# URESP_PULSER.net
KiCad netlist of a schematic drawn in Altium Designer
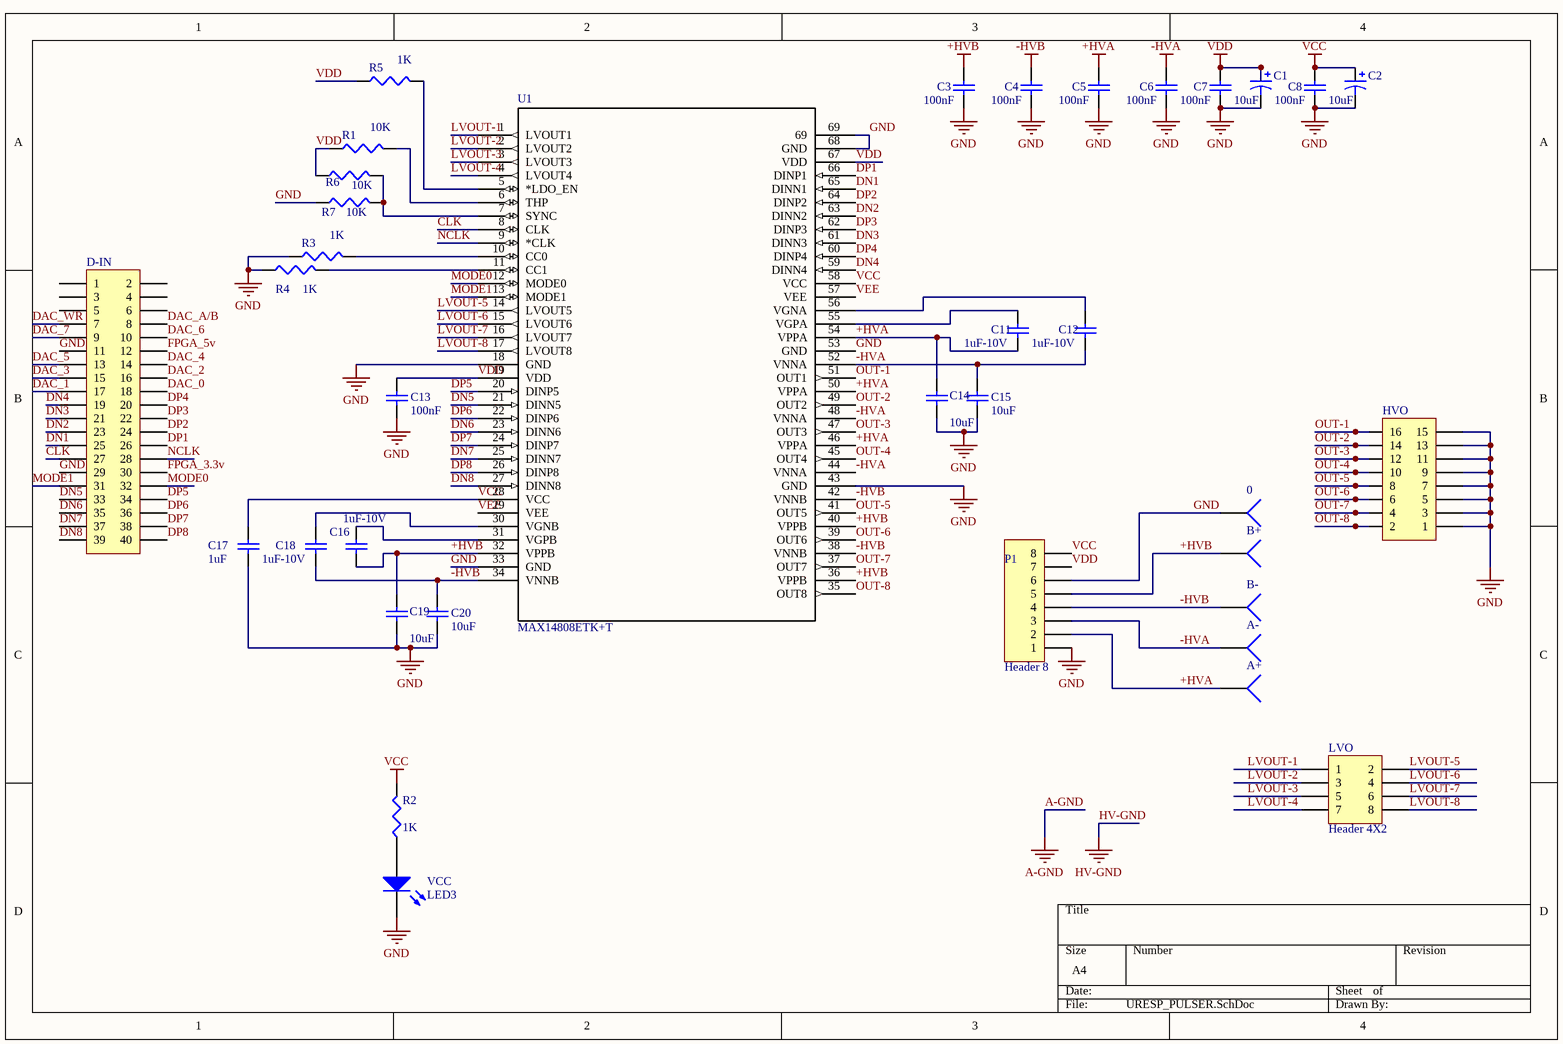
[diagram p0: URESP_PULSER.SchDoc]

(export (version "E")
  (design (tool "Eeschema 10.0.6"))
  (components
    (comp (ref "0")
      (value "~")
      (footprint "PIN1")
      (description "Socket")
      (fields (field (name "PUBLISHER") "Altium Limited"))
      (libsource (lib "Miscellaneous Connectors") (part "Socket"))
    )
    (comp (ref "A+")
      (value "~")
      (footprint "PIN1")
      (description "Socket")
      (fields (field (name "PUBLISHER") "Altium Limited"))
      (libsource (lib "Miscellaneous Connectors") (part "Socket"))
    )
    (comp (ref "A-")
      (value "~")
      (footprint "PIN1")
      (description "Socket")
      (fields (field (name "PUBLISHER") "Altium Limited"))
      (libsource (lib "Miscellaneous Connectors") (part "Socket"))
    )
    (comp (ref "B+")
      (value "~")
      (footprint "PIN1")
      (description "Socket")
      (fields (field (name "PUBLISHER") "Altium Limited"))
      (libsource (lib "Miscellaneous Connectors") (part "Socket"))
    )
    (comp (ref "B-")
      (value "~")
      (footprint "PIN1")
      (description "Socket")
      (fields (field (name "PUBLISHER") "Altium Limited"))
      (libsource (lib "Miscellaneous Connectors") (part "Socket"))
    )
    (comp (ref "C1")
      (value "10uF")
      (footprint "C1206")
      (description "Polarized Capacitor (Surface Mount)")
      (fields (field (name "PUBLISHER") "Altium Limited"))
      (libsource (lib "Miscellaneous Devices") (part "Cap Pol3"))
    )
    (comp (ref "C2")
      (value "10uF")
      (footprint "C1206")
      (description "Polarized Capacitor (Surface Mount)")
      (fields (field (name "PUBLISHER") "Altium Limited"))
      (libsource (lib "Miscellaneous Devices") (part "Cap Pol3"))
    )
    (comp (ref "C3")
      (value "100nF")
      (footprint "6-0805_M")
      (description "Capacitor (Semiconductor SIM Model)")
      (fields (field (name "PUBLISHER") "Altium Limited"))
      (libsource (lib "Miscellaneous Devices") (part "Cap Semi"))
    )
    (comp (ref "C4")
      (value "100nF")
      (footprint "6-0805_M")
      (description "Capacitor (Semiconductor SIM Model)")
      (fields (field (name "PUBLISHER") "Altium Limited"))
      (libsource (lib "Miscellaneous Devices") (part "Cap Semi"))
    )
    (comp (ref "C5")
      (value "100nF")
      (footprint "6-0805_M")
      (description "Capacitor (Semiconductor SIM Model)")
      (fields (field (name "PUBLISHER") "Altium Limited"))
      (libsource (lib "Miscellaneous Devices") (part "Cap Semi"))
    )
    (comp (ref "C6")
      (value "100nF")
      (footprint "6-0805_M")
      (description "Capacitor (Semiconductor SIM Model)")
      (fields (field (name "PUBLISHER") "Altium Limited"))
      (libsource (lib "Miscellaneous Devices") (part "Cap Semi"))
    )
    (comp (ref "C7")
      (value "100nF")
      (footprint "1608[0603]")
      (description "Capacitor (Semiconductor SIM Model)")
      (fields (field (name "PUBLISHER") "Altium Limited"))
      (libsource (lib "Miscellaneous Devices") (part "Cap Semi"))
    )
    (comp (ref "C8")
      (value "100nF")
      (footprint "1608[0603]")
      (description "Capacitor (Semiconductor SIM Model)")
      (fields (field (name "PUBLISHER") "Altium Limited"))
      (libsource (lib "Miscellaneous Devices") (part "Cap Semi"))
    )
    (comp (ref "C11")
      (value "1uF-10V")
      (footprint "1608[0603]")
      (description "Capacitor (Semiconductor SIM Model)")
      (fields (field (name "PUBLISHER") "Altium Limited"))
      (libsource (lib "Miscellaneous Devices") (part "Cap Semi"))
    )
    (comp (ref "C12")
      (value "1uF-10V")
      (footprint "1608[0603]")
      (description "Capacitor (Semiconductor SIM Model)")
      (fields (field (name "PUBLISHER") "Altium Limited"))
      (libsource (lib "Miscellaneous Devices") (part "Cap Semi"))
    )
    (comp (ref "C13")
      (value "100nF")
      (footprint "1608[0603]")
      (description "Capacitor (Semiconductor SIM Model)")
      (fields (field (name "PUBLISHER") "Altium Limited"))
      (libsource (lib "Miscellaneous Devices") (part "Cap Semi"))
    )
    (comp (ref "C14")
      (value "10uF")
      (footprint "CAPPR5-6.3X5")
      (description "Capacitor (Semiconductor SIM Model)")
      (fields (field (name "PUBLISHER") "Altium Limited"))
      (libsource (lib "Miscellaneous Devices") (part "Cap Semi"))
    )
    (comp (ref "C15")
      (value "10uF")
      (footprint "CAPPR5-6.3x5")
      (description "Capacitor (Semiconductor SIM Model)")
      (fields (field (name "PUBLISHER") "Altium Limited"))
      (libsource (lib "Miscellaneous Devices") (part "Cap Semi"))
    )
    (comp (ref "C16")
      (value "1uF-10V")
      (footprint "1608[0603]")
      (description "Capacitor (Semiconductor SIM Model)")
      (fields (field (name "PUBLISHER") "Altium Limited"))
      (libsource (lib "Miscellaneous Devices") (part "Cap Semi"))
    )
    (comp (ref "C17")
      (value "1uF")
      (footprint "1608[0603]")
      (description "Capacitor (Semiconductor SIM Model)")
      (fields (field (name "PUBLISHER") "Altium Limited"))
      (libsource (lib "Miscellaneous Devices") (part "Cap Semi"))
    )
    (comp (ref "C18")
      (value "1uF-10V")
      (footprint "1608[0603]")
      (description "Capacitor (Semiconductor SIM Model)")
      (fields (field (name "PUBLISHER") "Altium Limited"))
      (libsource (lib "Miscellaneous Devices") (part "Cap Semi"))
    )
    (comp (ref "C19")
      (value "10uF")
      (footprint "CAPPR5-6.3X5")
      (description "Capacitor (Semiconductor SIM Model)")
      (fields (field (name "PUBLISHER") "Altium Limited"))
      (libsource (lib "Miscellaneous Devices") (part "Cap Semi"))
    )
    (comp (ref "C20")
      (value "10uF")
      (footprint "CAPPR5-6.3X5")
      (description "Capacitor (Semiconductor SIM Model)")
      (fields (field (name "PUBLISHER") "Altium Limited"))
      (libsource (lib "Miscellaneous Devices") (part "Cap Semi"))
    )
    (comp (ref "D-IN")
      (value "~")
      (footprint "HDR2X20")
      (description "Header, 20-Pin, Dual row")
      (fields (field (name "PUBLISHER") "Altium Limited"))
      (libsource (lib "Miscellaneous Connectors") (part "Header 20X2"))
    )
    (comp (ref "HVO")
      (value "~")
      (footprint "HDR2X8")
      (description "Header, 8-Pin, Dual row, Right Angle")
      (fields (field (name "PUBLISHER") "Altium Limited"))
      (libsource (lib "Miscellaneous Connectors") (part "Header 8X2H"))
    )
    (comp (ref "LVO")
      (value "Header 4X2")
      (footprint "HDR2X4")
      (description "Header, 4-Pin, Dual row")
      (fields (field (name "PUBLISHER") "Altium Limited"))
      (libsource (lib "Miscellaneous Connectors") (part "Header 4X2"))
    )
    (comp (ref "P1")
      (value "Header 8")
      (footprint "HDR1X8")
      (description "Header, 8-Pin")
      (fields (field (name "PUBLISHER") "Altium Limited"))
      (libsource (lib "Miscellaneous Connectors") (part "Header 8"))
    )
    (comp (ref "R1")
      (value "10K")
      (footprint "J1-0603")
      (description "Resistor")
      (fields (field (name "PUBLISHER") "Altium Limited"))
      (libsource (lib "Miscellaneous Devices") (part "Res3"))
    )
    (comp (ref "R2")
      (value "1K")
      (footprint "J1-0603")
      (description "Resistor")
      (fields (field (name "PUBLISHER") "Altium Limited"))
      (libsource (lib "Miscellaneous Devices") (part "Res3"))
    )
    (comp (ref "R3")
      (value "1K")
      (footprint "J1-0603")
      (description "Resistor")
      (fields (field (name "PUBLISHER") "Altium Limited"))
      (libsource (lib "Miscellaneous Devices") (part "Res3"))
    )
    (comp (ref "R4")
      (value "1K")
      (footprint "J1-0603")
      (description "Resistor")
      (fields (field (name "PUBLISHER") "Altium Limited"))
      (libsource (lib "Miscellaneous Devices") (part "Res3"))
    )
    (comp (ref "R5")
      (value "1K")
      (footprint "J1-0603")
      (description "Resistor")
      (fields (field (name "PUBLISHER") "Altium Limited"))
      (libsource (lib "Miscellaneous Devices") (part "Res3"))
    )
    (comp (ref "R6")
      (value "10K")
      (footprint "J1-0603")
      (description "Resistor")
      (fields (field (name "PUBLISHER") "Altium Limited"))
      (libsource (lib "Miscellaneous Devices") (part "Res3"))
    )
    (comp (ref "R7")
      (value "10K")
      (footprint "J1-0603")
      (description "Resistor")
      (fields (field (name "PUBLISHER") "Altium Limited"))
      (libsource (lib "Miscellaneous Devices") (part "Res3"))
    )
    (comp (ref "U1")
      (value "MAX14808ETK+T")
      (footprint "21-0142E_T6800-2")
      (description "Imported")
      (libsource (lib "max14808") (part "MAX14808ETK+T"))
    )
    (comp (ref "VCC")
      (value "LED3")
      (footprint "6-0805_M")
      (description "Typical BLUE SiC LED")
      (fields (field (name "PUBLISHER") "Altium Limited"))
      (libsource (lib "Miscellaneous Devices") (part "LED3"))
    )
  )
  (nets
    (net (code "1") (name "+HVA") (class "Default")
      (node (ref "A+") (pin "1") (pinfunction "1_1") (pintype "passive"))
      (node (ref "C11") (pin "1") (pinfunction "1_1") (pintype "passive"))
      (node (ref "C14") (pin "1") (pinfunction "1_1") (pintype "passive"))
      (node (ref "C5") (pin "2") (pinfunction "2_2") (pintype "passive"))
      (node (ref "P1") (pin "2") (pinfunction "2_2") (pintype "passive"))
      (node (ref "U1") (pin "46") (pinfunction "VPPA_46") (pintype "power_in"))
      (node (ref "U1") (pin "50") (pinfunction "VPPA_50") (pintype "power_in"))
      (node (ref "U1") (pin "54") (pinfunction "VPPA_54") (pintype "power_in"))
    )
    (net (code "2") (name "+HVB") (class "Default")
      (node (ref "B+") (pin "1") (pinfunction "1_1") (pintype "passive"))
      (node (ref "C16") (pin "1") (pinfunction "1_1") (pintype "passive"))
      (node (ref "C19") (pin "1") (pinfunction "1_1") (pintype "passive"))
      (node (ref "C3") (pin "2") (pinfunction "2_2") (pintype "passive"))
      (node (ref "P1") (pin "5") (pinfunction "5_5") (pintype "passive"))
      (node (ref "U1") (pin "32") (pinfunction "VPPB_32") (pintype "power_in"))
      (node (ref "U1") (pin "36") (pinfunction "VPPB_36") (pintype "power_in"))
      (node (ref "U1") (pin "40") (pinfunction "VPPB_40") (pintype "power_in"))
    )
    (net (code "3") (name "-HVA") (class "Default")
      (node (ref "A-") (pin "1") (pinfunction "1_1") (pintype "passive"))
      (node (ref "C12") (pin "1") (pinfunction "1_1") (pintype "passive"))
      (node (ref "C15") (pin "2") (pinfunction "2_2") (pintype "passive"))
      (node (ref "C6") (pin "2") (pinfunction "2_2") (pintype "passive"))
      (node (ref "P1") (pin "3") (pinfunction "3_3") (pintype "passive"))
      (node (ref "U1") (pin "44") (pinfunction "VNNA_44") (pintype "power_in"))
      (node (ref "U1") (pin "48") (pinfunction "VNNA_48") (pintype "power_in"))
      (node (ref "U1") (pin "52") (pinfunction "VNNA_52") (pintype "power_in"))
    )
    (net (code "4") (name "-HVB") (class "Default")
      (node (ref "B-") (pin "1") (pinfunction "1_1") (pintype "passive"))
      (node (ref "C18") (pin "1") (pinfunction "1_1") (pintype "passive"))
      (node (ref "C20") (pin "2") (pinfunction "2_2") (pintype "passive"))
      (node (ref "C4") (pin "2") (pinfunction "2_2") (pintype "passive"))
      (node (ref "P1") (pin "4") (pinfunction "4_4") (pintype "passive"))
      (node (ref "U1") (pin "34") (pinfunction "VNNB_34") (pintype "power_in"))
      (node (ref "U1") (pin "38") (pinfunction "VNNB_38") (pintype "power_in"))
      (node (ref "U1") (pin "42") (pinfunction "VNNB_42") (pintype "power_in"))
    )
    (net (code "5") (name "/CLK") (class "Default")
      (node (ref "D-IN") (pin "27") (pinfunction "27_27") (pintype "passive"))
      (node (ref "U1") (pin "8") (pinfunction "CLK_8") (pintype "bidirectional"))
    )
    (net (code "6") (name "/DAC_0") (class "Default")
      (node (ref "D-IN") (pin "18") (pinfunction "18_18") (pintype "passive"))
    )
    (net (code "7") (name "/DAC_1") (class "Default")
      (node (ref "D-IN") (pin "17") (pinfunction "17_17") (pintype "passive"))
    )
    (net (code "8") (name "/DAC_2") (class "Default")
      (node (ref "D-IN") (pin "16") (pinfunction "16_16") (pintype "passive"))
    )
    (net (code "9") (name "/DAC_3") (class "Default")
      (node (ref "D-IN") (pin "15") (pinfunction "15_15") (pintype "passive"))
    )
    (net (code "10") (name "/DAC_4") (class "Default")
      (node (ref "D-IN") (pin "14") (pinfunction "14_14") (pintype "passive"))
    )
    (net (code "11") (name "/DAC_5") (class "Default")
      (node (ref "D-IN") (pin "13") (pinfunction "13_13") (pintype "passive"))
    )
    (net (code "12") (name "/DAC_6") (class "Default")
      (node (ref "D-IN") (pin "10") (pinfunction "10_10") (pintype "passive"))
    )
    (net (code "13") (name "/DAC_7") (class "Default")
      (node (ref "D-IN") (pin "9") (pinfunction "9_9") (pintype "passive"))
    )
    (net (code "14") (name "/DAC_A{slash}B") (class "Default")
      (node (ref "D-IN") (pin "8") (pinfunction "8_8") (pintype "passive"))
    )
    (net (code "15") (name "/DAC_WR") (class "Default")
      (node (ref "D-IN") (pin "7") (pinfunction "7_7") (pintype "passive"))
    )
    (net (code "16") (name "/DN1") (class "Default")
      (node (ref "D-IN") (pin "25") (pinfunction "25_25") (pintype "passive"))
      (node (ref "U1") (pin "65") (pinfunction "DINN1_65") (pintype "input"))
    )
    (net (code "17") (name "/DN2") (class "Default")
      (node (ref "D-IN") (pin "23") (pinfunction "23_23") (pintype "passive"))
      (node (ref "U1") (pin "63") (pinfunction "DINN2_63") (pintype "input"))
    )
    (net (code "18") (name "/DN3") (class "Default")
      (node (ref "D-IN") (pin "21") (pinfunction "21_21") (pintype "passive"))
      (node (ref "U1") (pin "61") (pinfunction "DINN3_61") (pintype "input"))
    )
    (net (code "19") (name "/DN4") (class "Default")
      (node (ref "D-IN") (pin "19") (pinfunction "19_19") (pintype "passive"))
      (node (ref "U1") (pin "59") (pinfunction "DINN4_59") (pintype "input"))
    )
    (net (code "20") (name "/DN5") (class "Default")
      (node (ref "D-IN") (pin "33") (pinfunction "33_33") (pintype "passive"))
      (node (ref "U1") (pin "21") (pinfunction "DINN5_21") (pintype "input"))
    )
    (net (code "21") (name "/DN6") (class "Default")
      (node (ref "D-IN") (pin "35") (pinfunction "35_35") (pintype "passive"))
      (node (ref "U1") (pin "23") (pinfunction "DINN6_23") (pintype "input"))
    )
    (net (code "22") (name "/DN7") (class "Default")
      (node (ref "D-IN") (pin "37") (pinfunction "37_37") (pintype "passive"))
      (node (ref "U1") (pin "25") (pinfunction "DINN7_25") (pintype "input"))
    )
    (net (code "23") (name "/DN8") (class "Default")
      (node (ref "D-IN") (pin "39") (pinfunction "39_39") (pintype "passive"))
      (node (ref "U1") (pin "27") (pinfunction "DINN8_27") (pintype "input"))
    )
    (net (code "24") (name "/DP1") (class "Default")
      (node (ref "D-IN") (pin "26") (pinfunction "26_26") (pintype "passive"))
      (node (ref "U1") (pin "66") (pinfunction "DINP1_66") (pintype "input"))
    )
    (net (code "25") (name "/DP2") (class "Default")
      (node (ref "D-IN") (pin "24") (pinfunction "24_24") (pintype "passive"))
      (node (ref "U1") (pin "64") (pinfunction "DINP2_64") (pintype "input"))
    )
    (net (code "26") (name "/DP3") (class "Default")
      (node (ref "D-IN") (pin "22") (pinfunction "22_22") (pintype "passive"))
      (node (ref "U1") (pin "62") (pinfunction "DINP3_62") (pintype "input"))
    )
    (net (code "27") (name "/DP4") (class "Default")
      (node (ref "D-IN") (pin "20") (pinfunction "20_20") (pintype "passive"))
      (node (ref "U1") (pin "60") (pinfunction "DINP4_60") (pintype "input"))
    )
    (net (code "28") (name "/DP5") (class "Default")
      (node (ref "D-IN") (pin "34") (pinfunction "34_34") (pintype "passive"))
      (node (ref "U1") (pin "20") (pinfunction "DINP5_20") (pintype "input"))
    )
    (net (code "29") (name "/DP6") (class "Default")
      (node (ref "D-IN") (pin "36") (pinfunction "36_36") (pintype "passive"))
      (node (ref "U1") (pin "22") (pinfunction "DINP6_22") (pintype "input"))
    )
    (net (code "30") (name "/DP7") (class "Default")
      (node (ref "D-IN") (pin "38") (pinfunction "38_38") (pintype "passive"))
      (node (ref "U1") (pin "24") (pinfunction "DINP7_24") (pintype "input"))
    )
    (net (code "31") (name "/DP8") (class "Default")
      (node (ref "D-IN") (pin "40") (pinfunction "40_40") (pintype "passive"))
      (node (ref "U1") (pin "26") (pinfunction "DINP8_26") (pintype "input"))
    )
    (net (code "32") (name "/FPGA_3.3v") (class "Default")
      (node (ref "D-IN") (pin "30") (pinfunction "30_30") (pintype "passive"))
    )
    (net (code "33") (name "/FPGA_5v") (class "Default")
      (node (ref "D-IN") (pin "12") (pinfunction "12_12") (pintype "passive"))
    )
    (net (code "34") (name "/LVOUT-1") (class "Default")
      (node (ref "LVO") (pin "1") (pinfunction "1_1") (pintype "passive"))
      (node (ref "U1") (pin "1") (pinfunction "LVOUT1_1") (pintype "output"))
    )
    (net (code "35") (name "/LVOUT-2") (class "Default")
      (node (ref "LVO") (pin "3") (pinfunction "3_3") (pintype "passive"))
      (node (ref "U1") (pin "2") (pinfunction "LVOUT2_2") (pintype "output"))
    )
    (net (code "36") (name "/LVOUT-3") (class "Default")
      (node (ref "LVO") (pin "5") (pinfunction "5_5") (pintype "passive"))
      (node (ref "U1") (pin "3") (pinfunction "LVOUT3_3") (pintype "output"))
    )
    (net (code "37") (name "/LVOUT-4") (class "Default")
      (node (ref "LVO") (pin "7") (pinfunction "7_7") (pintype "passive"))
      (node (ref "U1") (pin "4") (pinfunction "LVOUT4_4") (pintype "output"))
    )
    (net (code "38") (name "/LVOUT-5") (class "Default")
      (node (ref "LVO") (pin "2") (pinfunction "2_2") (pintype "passive"))
      (node (ref "U1") (pin "14") (pinfunction "LVOUT5_14") (pintype "output"))
    )
    (net (code "39") (name "/LVOUT-6") (class "Default")
      (node (ref "LVO") (pin "4") (pinfunction "4_4") (pintype "passive"))
      (node (ref "U1") (pin "15") (pinfunction "LVOUT6_15") (pintype "output"))
    )
    (net (code "40") (name "/LVOUT-7") (class "Default")
      (node (ref "LVO") (pin "6") (pinfunction "6_6") (pintype "passive"))
      (node (ref "U1") (pin "16") (pinfunction "LVOUT7_16") (pintype "output"))
    )
    (net (code "41") (name "/LVOUT-8") (class "Default")
      (node (ref "LVO") (pin "8") (pinfunction "8_8") (pintype "passive"))
      (node (ref "U1") (pin "17") (pinfunction "LVOUT8_17") (pintype "output"))
    )
    (net (code "42") (name "/MODE0") (class "Default")
      (node (ref "D-IN") (pin "32") (pinfunction "32_32") (pintype "passive"))
      (node (ref "U1") (pin "12") (pinfunction "MODE0_12") (pintype "bidirectional"))
    )
    (net (code "43") (name "/MODE1") (class "Default")
      (node (ref "D-IN") (pin "31") (pinfunction "31_31") (pintype "passive"))
      (node (ref "U1") (pin "13") (pinfunction "MODE1_13") (pintype "bidirectional"))
    )
    (net (code "44") (name "/NCLK") (class "Default")
      (node (ref "D-IN") (pin "28") (pinfunction "28_28") (pintype "passive"))
      (node (ref "U1") (pin "9") (pinfunction "*CLK_9") (pintype "bidirectional"))
    )
    (net (code "45") (name "/OUT-1") (class "Default")
      (node (ref "HVO") (pin "16") (pinfunction "16_16") (pintype "passive"))
      (node (ref "U1") (pin "51") (pinfunction "OUT1_51") (pintype "output"))
    )
    (net (code "46") (name "/OUT-2") (class "Default")
      (node (ref "HVO") (pin "14") (pinfunction "14_14") (pintype "passive"))
      (node (ref "U1") (pin "49") (pinfunction "OUT2_49") (pintype "output"))
    )
    (net (code "47") (name "/OUT-3") (class "Default")
      (node (ref "HVO") (pin "12") (pinfunction "12_12") (pintype "passive"))
      (node (ref "U1") (pin "47") (pinfunction "OUT3_47") (pintype "output"))
    )
    (net (code "48") (name "/OUT-4") (class "Default")
      (node (ref "HVO") (pin "10") (pinfunction "10_10") (pintype "passive"))
      (node (ref "U1") (pin "45") (pinfunction "OUT4_45") (pintype "output"))
    )
    (net (code "49") (name "/OUT-5") (class "Default")
      (node (ref "HVO") (pin "8") (pinfunction "8_8") (pintype "passive"))
      (node (ref "U1") (pin "41") (pinfunction "OUT5_41") (pintype "output"))
    )
    (net (code "50") (name "/OUT-6") (class "Default")
      (node (ref "HVO") (pin "6") (pinfunction "6_6") (pintype "passive"))
      (node (ref "U1") (pin "39") (pinfunction "OUT6_39") (pintype "output"))
    )
    (net (code "51") (name "/OUT-7") (class "Default")
      (node (ref "HVO") (pin "4") (pinfunction "4_4") (pintype "passive"))
      (node (ref "U1") (pin "37") (pinfunction "OUT7_37") (pintype "output"))
    )
    (net (code "52") (name "/OUT-8") (class "Default")
      (node (ref "HVO") (pin "2") (pinfunction "2_2") (pintype "passive"))
      (node (ref "U1") (pin "35") (pinfunction "OUT8_35") (pintype "output"))
    )
    (net (code "53") (name "/VEE") (class "Default")
      (node (ref "U1") (pin "29") (pinfunction "VEE_29") (pintype "power_in"))
      (node (ref "U1") (pin "57") (pinfunction "VEE_57") (pintype "power_in"))
    )
    (net (code "55") (name "GND") (class "Default")
      (node (ref "0") (pin "1") (pinfunction "1_1") (pintype "passive"))
      (node (ref "C1") (pin "2") (pinfunction "2_2") (pintype "passive"))
      (node (ref "C13") (pin "1") (pinfunction "1_1") (pintype "passive"))
      (node (ref "C14") (pin "2") (pinfunction "2_2") (pintype "passive"))
      (node (ref "C15") (pin "1") (pinfunction "1_1") (pintype "passive"))
      (node (ref "C17") (pin "1") (pinfunction "1_1") (pintype "passive"))
      (node (ref "C19") (pin "2") (pinfunction "2_2") (pintype "passive"))
      (node (ref "C2") (pin "2") (pinfunction "2_2") (pintype "passive"))
      (node (ref "C20") (pin "1") (pinfunction "1_1") (pintype "passive"))
      (node (ref "C3") (pin "1") (pinfunction "1_1") (pintype "passive"))
      (node (ref "C4") (pin "1") (pinfunction "1_1") (pintype "passive"))
      (node (ref "C5") (pin "1") (pinfunction "1_1") (pintype "passive"))
      (node (ref "C6") (pin "1") (pinfunction "1_1") (pintype "passive"))
      (node (ref "C7") (pin "1") (pinfunction "1_1") (pintype "passive"))
      (node (ref "C8") (pin "1") (pinfunction "1_1") (pintype "passive"))
      (node (ref "D-IN") (pin "11") (pinfunction "11_11") (pintype "passive"))
      (node (ref "D-IN") (pin "29") (pinfunction "29_29") (pintype "passive"))
      (node (ref "HVO") (pin "1") (pinfunction "1_1") (pintype "passive"))
      (node (ref "HVO") (pin "11") (pinfunction "11_11") (pintype "passive"))
      (node (ref "HVO") (pin "13") (pinfunction "13_13") (pintype "passive"))
      (node (ref "HVO") (pin "15") (pinfunction "15_15") (pintype "passive"))
      (node (ref "HVO") (pin "3") (pinfunction "3_3") (pintype "passive"))
      (node (ref "HVO") (pin "5") (pinfunction "5_5") (pintype "passive"))
      (node (ref "HVO") (pin "7") (pinfunction "7_7") (pintype "passive"))
      (node (ref "HVO") (pin "9") (pinfunction "9_9") (pintype "passive"))
      (node (ref "P1") (pin "1") (pinfunction "1_1") (pintype "passive"))
      (node (ref "P1") (pin "6") (pinfunction "6_6") (pintype "passive"))
      (node (ref "R3") (pin "1") (pinfunction "1_1") (pintype "passive"))
      (node (ref "R4") (pin "1") (pinfunction "1_1") (pintype "passive"))
      (node (ref "R7") (pin "1") (pinfunction "1_1") (pintype "passive"))
      (node (ref "U1") (pin "18") (pinfunction "GND_18") (pintype "power_in"))
      (node (ref "U1") (pin "33") (pinfunction "GND_33") (pintype "power_in"))
      (node (ref "U1") (pin "43") (pinfunction "GND_43") (pintype "power_in"))
      (node (ref "U1") (pin "53") (pinfunction "GND_53") (pintype "power_in"))
      (node (ref "U1") (pin "68") (pinfunction "GND_68") (pintype "power_in"))
      (node (ref "U1") (pin "69") (pinfunction "69_69") (pintype "passive"))
      (node (ref "VCC") (pin "2") (pinfunction "K_2") (pintype "passive"))
    )
    (net (code "57") (name "Net-(U1-*LDO_EN)") (class "Default")
      (node (ref "R5") (pin "2") (pinfunction "2_2") (pintype "passive"))
      (node (ref "U1") (pin "5") (pinfunction "*LDO_EN_5") (pintype "bidirectional"))
    )
    (net (code "58") (name "Net-(U1-CC0)") (class "Default")
      (node (ref "R3") (pin "2") (pinfunction "2_2") (pintype "passive"))
      (node (ref "U1") (pin "10") (pinfunction "CC0_10") (pintype "bidirectional"))
    )
    (net (code "59") (name "Net-(U1-CC1)") (class "Default")
      (node (ref "R4") (pin "2") (pinfunction "2_2") (pintype "passive"))
      (node (ref "U1") (pin "11") (pinfunction "CC1_11") (pintype "bidirectional"))
    )
    (net (code "60") (name "Net-(U1-SYNC)") (class "Default")
      (node (ref "R6") (pin "2") (pinfunction "2_2") (pintype "passive"))
      (node (ref "R7") (pin "2") (pinfunction "2_2") (pintype "passive"))
      (node (ref "U1") (pin "7") (pinfunction "SYNC_7") (pintype "bidirectional"))
    )
    (net (code "61") (name "Net-(U1-THP)") (class "Default")
      (node (ref "R1") (pin "2") (pinfunction "2_2") (pintype "passive"))
      (node (ref "U1") (pin "6") (pinfunction "THP_6") (pintype "bidirectional"))
    )
    (net (code "62") (name "Net-(U1-VGNA)") (class "Default")
      (node (ref "C12") (pin "2") (pinfunction "2_2") (pintype "passive"))
      (node (ref "U1") (pin "56") (pinfunction "VGNA_56") (pintype "power_in"))
    )
    (net (code "63") (name "Net-(U1-VGNB)") (class "Default")
      (node (ref "C18") (pin "2") (pinfunction "2_2") (pintype "passive"))
      (node (ref "U1") (pin "30") (pinfunction "VGNB_30") (pintype "power_in"))
    )
    (net (code "64") (name "Net-(U1-VGPA)") (class "Default")
      (node (ref "C11") (pin "2") (pinfunction "2_2") (pintype "passive"))
      (node (ref "U1") (pin "55") (pinfunction "VGPA_55") (pintype "power_in"))
    )
    (net (code "65") (name "Net-(U1-VGPB)") (class "Default")
      (node (ref "C16") (pin "2") (pinfunction "2_2") (pintype "passive"))
      (node (ref "U1") (pin "31") (pinfunction "VGPB_31") (pintype "power_in"))
    )
    (net (code "66") (name "Net-(VCC-A)") (class "Default")
      (node (ref "R2") (pin "1") (pinfunction "1_1") (pintype "passive"))
      (node (ref "VCC") (pin "1") (pinfunction "A_1") (pintype "passive"))
    )
    (net (code "67") (name "VCC") (class "Default")
      (node (ref "C17") (pin "2") (pinfunction "2_2") (pintype "passive"))
      (node (ref "C2") (pin "1") (pinfunction "1_1") (pintype "passive"))
      (node (ref "C8") (pin "2") (pinfunction "2_2") (pintype "passive"))
      (node (ref "P1") (pin "8") (pinfunction "8_8") (pintype "passive"))
      (node (ref "R2") (pin "2") (pinfunction "2_2") (pintype "passive"))
      (node (ref "U1") (pin "28") (pinfunction "VCC_28") (pintype "power_in"))
      (node (ref "U1") (pin "58") (pinfunction "VCC_58") (pintype "power_in"))
    )
    (net (code "68") (name "VDD") (class "Default")
      (node (ref "C1") (pin "1") (pinfunction "1_1") (pintype "passive"))
      (node (ref "C13") (pin "2") (pinfunction "2_2") (pintype "passive"))
      (node (ref "C7") (pin "2") (pinfunction "2_2") (pintype "passive"))
      (node (ref "P1") (pin "7") (pinfunction "7_7") (pintype "passive"))
      (node (ref "R1") (pin "1") (pinfunction "1_1") (pintype "passive"))
      (node (ref "R5") (pin "1") (pinfunction "1_1") (pintype "passive"))
      (node (ref "R6") (pin "1") (pinfunction "1_1") (pintype "passive"))
      (node (ref "U1") (pin "19") (pinfunction "VDD_19") (pintype "power_in"))
      (node (ref "U1") (pin "67") (pinfunction "VDD_67") (pintype "power_in"))
    )
    (net (code "69") (name "unconnected-(D-IN-Pad1)") (class "Default")
      (node (ref "D-IN") (pin "1") (pinfunction "1_1") (pintype "passive"))
    )
    (net (code "70") (name "unconnected-(D-IN-Pad2)") (class "Default")
      (node (ref "D-IN") (pin "2") (pinfunction "2_2") (pintype "passive"))
    )
    (net (code "71") (name "unconnected-(D-IN-Pad3)") (class "Default")
      (node (ref "D-IN") (pin "3") (pinfunction "3_3") (pintype "passive"))
    )
    (net (code "72") (name "unconnected-(D-IN-Pad4)") (class "Default")
      (node (ref "D-IN") (pin "4") (pinfunction "4_4") (pintype "passive"))
    )
    (net (code "73") (name "unconnected-(D-IN-Pad5)") (class "Default")
      (node (ref "D-IN") (pin "5") (pinfunction "5_5") (pintype "passive"))
    )
    (net (code "74") (name "unconnected-(D-IN-Pad6)") (class "Default")
      (node (ref "D-IN") (pin "6") (pinfunction "6_6") (pintype "passive"))
    )
  )
)
